# EasyEDA_esp8266-ed_fan_2020-07-05_01-05-.net
KiCad netlist of a schematic drawn in EasyEDA
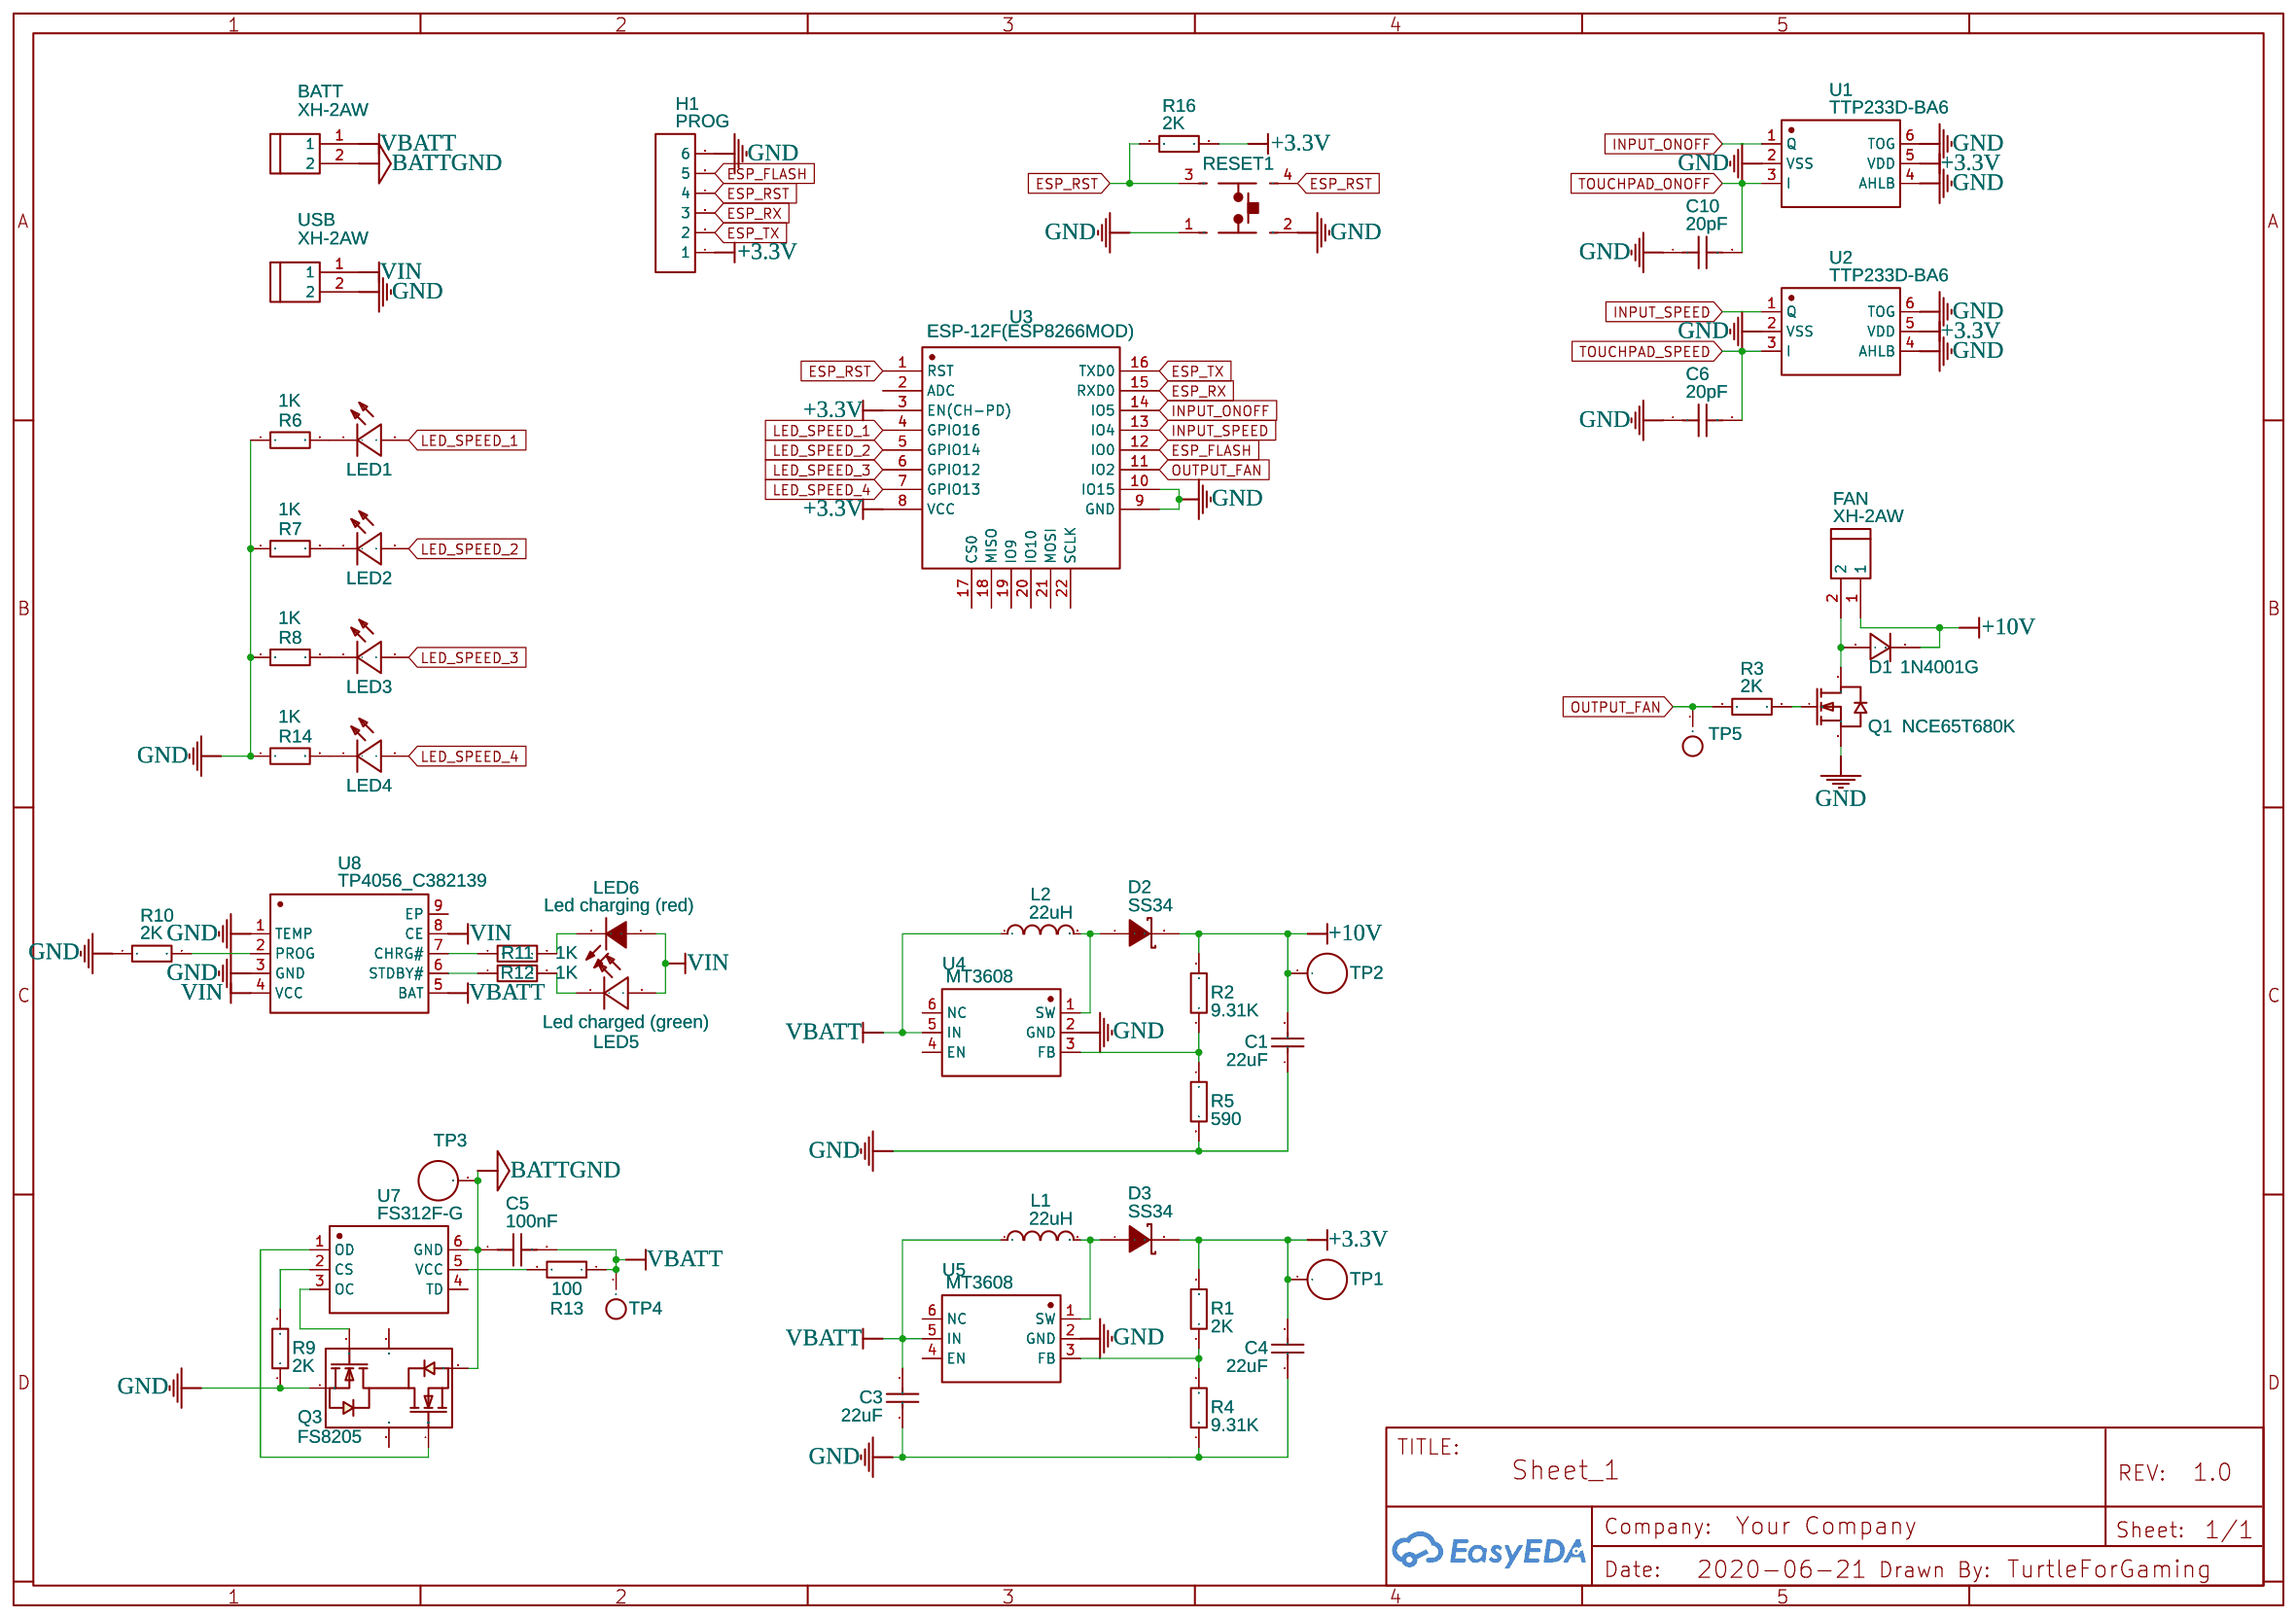
[diagram p0: schematic sheet]

(export (version "E")
  (design (tool "Eeschema 10.0.6"))
  (components
    (comp (ref "BATT")
      (value "XH-2AW")
      (fields (field (name "BOM_Supplier Part") "C33132"))
      (libsource (lib "") (part "XH-2AW"))
    )
    (comp (ref "C1")
      (value "22uF")
      (fields
        (field (name "BOM_Manufacturer Part") "1812X226K250NT")
        (field (name "BOM_Supplier Part") "C28504")
      )
      (libsource (lib "") (part "Unknown_645_-290"))
    )
    (comp (ref "C3")
      (value "22uF")
      (fields
        (field (name "BOM_Manufacturer Part") "1812X226K250NT")
        (field (name "BOM_Supplier Part") "C28504")
      )
      (libsource (lib "") (part "Unknown_450_-110"))
    )
    (comp (ref "C4")
      (value "22uF")
      (fields
        (field (name "BOM_Manufacturer Part") "1812X226K250NT")
        (field (name "BOM_Supplier Part") "C28504")
      )
      (libsource (lib "") (part "Unknown_645_-135"))
    )
    (comp (ref "C5")
      (value "100nF")
      (fields
        (field (name "BOM_Manufacturer Part") "GRM21BR72A104KAC4L")
        (field (name "BOM_Supplier Part") "C86044")
      )
      (libsource (lib "") (part "GRM21BR72A104KAC4L"))
    )
    (comp (ref "C6")
      (value "20pF")
      (fields
        (field (name "BOM_Manufacturer Part") "0603N200J500")
        (field (name "BOM_Supplier Part") "C123543")
      )
      (libsource (lib "") (part "0603N200J500"))
    )
    (comp (ref "C10")
      (value "20pF")
      (fields
        (field (name "BOM_Manufacturer Part") "0603N200J500")
        (field (name "BOM_Supplier Part") "C123543")
      )
      (libsource (lib "") (part "0603N200J500"))
    )
    (comp (ref "D1")
      (value "1N4001G")
      (fields (field (name "BOM_Supplier Part") "C433392"))
      (libsource (lib "") (part "1N4001G"))
    )
    (comp (ref "D2")
      (value "SS34")
      (fields (field (name "BOM_Supplier Part") "C8678"))
      (libsource (lib "") (part "Unknown_570_-340"))
    )
    (comp (ref "D3")
      (value "SS34")
      (fields (field (name "BOM_Supplier Part") "C8678"))
      (libsource (lib "") (part "Unknown_570_-185"))
    )
    (comp (ref "FAN")
      (value "XH-2AW")
      (fields (field (name "BOM_Supplier Part") "C33132"))
      (libsource (lib "") (part "XH-2AW_1"))
    )
    (comp (ref "H1")
      (value "PROG")
      (fields
        (field (name "BOM_Manufacturer Part") "Header-Male-2.54_1x6")
        (field (name "BOM_Supplier Part") "C37208")
      )
      (libsource (lib "") (part "Header-Male-2.54_1x6"))
    )
    (comp (ref "L1")
      (value "22uH")
      (fields
        (field (name "BOM_Manufacturer Part") "SMRH74-220MT")
        (field (name "BOM_Supplier Part") "C27442")
      )
      (libsource (lib "") (part "Unknown_520_-185"))
    )
    (comp (ref "L2")
      (value "22uH")
      (fields
        (field (name "BOM_Manufacturer Part") "SMRH74-220MT")
        (field (name "BOM_Supplier Part") "C27442")
      )
      (libsource (lib "") (part "Unknown_520_-340"))
    )
    (comp (ref "LED1")
      (value "Led charged (green)")
      (fields (field (name "BOM_Supplier Part") "C192319"))
      (libsource (lib "") (part "led Green"))
    )
    (comp (ref "LED2")
      (value "Led charged (green)")
      (fields (field (name "BOM_Supplier Part") "C192319"))
      (libsource (lib "") (part "led Green"))
    )
    (comp (ref "LED3")
      (value "Led charged (green)")
      (fields (field (name "BOM_Supplier Part") "C192319"))
      (libsource (lib "") (part "led Green"))
    )
    (comp (ref "LED4")
      (value "Led charged (green)")
      (fields (field (name "BOM_Supplier Part") "C192319"))
      (libsource (lib "") (part "led Green"))
    )
    (comp (ref "LED5")
      (value "Led charged (green)")
      (fields (field (name "BOM_Supplier Part") "C192319"))
      (libsource (lib "") (part "led Green"))
    )
    (comp (ref "LED6")
      (value "Led charging (red)")
      (fields (field (name "BOM_Supplier Part") "C192318"))
      (libsource (lib "") (part "KT-1206Red LED"))
    )
    (comp (ref "Q1")
      (value "NCE65T680K")
      (fields (field (name "BOM_Supplier Part") "C216787"))
      (libsource (lib "") (part "NCE65T680K"))
    )
    (comp (ref "Q3")
      (value "FS8205")
      (fields (field (name "BOM_Supplier Part") "C32254"))
      (libsource (lib "") (part "Unknown_190_-110"))
    )
    (comp (ref "R1")
      (value "2K")
      (fields
        (field (name "BOM_Manufacturer Part") "CR0805-FX-2001ELF")
        (field (name "BOM_Supplier Part") "C203834")
      )
      (libsource (lib "") (part "CR0805-FX-2001ELF"))
    )
    (comp (ref "R2")
      (value "9.31K")
      (fields
        (field (name "BOM_Manufacturer Part") "RMC08059.31K1%N")
        (field (name "BOM_Supplier Part") "C325873")
      )
      (libsource (lib "") (part "RMC08059.31K1%N"))
    )
    (comp (ref "R3")
      (value "2K")
      (fields
        (field (name "BOM_Manufacturer Part") "CR0805-FX-2001ELF")
        (field (name "BOM_Supplier Part") "C203834")
      )
      (libsource (lib "") (part "CR0805-FX-2001ELF_1"))
    )
    (comp (ref "R4")
      (value "9.31K")
      (fields
        (field (name "BOM_Manufacturer Part") "RMC08059.31K1%N")
        (field (name "BOM_Supplier Part") "C325873")
      )
      (libsource (lib "") (part "RMC08059.31K1%N"))
    )
    (comp (ref "R5")
      (value "590")
      (fields
        (field (name "BOM_Manufacturer Part") "CR0805F85900G")
        (field (name "BOM_Supplier Part") "C101801")
      )
      (libsource (lib "") (part "CR0805F85900G"))
    )
    (comp (ref "R6")
      (value "1K")
      (fields
        (field (name "BOM_Manufacturer Part") "CR0805J80102G")
        (field (name "BOM_Supplier Part") "C328385")
      )
      (libsource (lib "") (part "CR0805J80102G"))
    )
    (comp (ref "R7")
      (value "1K")
      (fields
        (field (name "BOM_Manufacturer Part") "CR0805J80102G")
        (field (name "BOM_Supplier Part") "C328385")
      )
      (libsource (lib "") (part "CR0805J80102G"))
    )
    (comp (ref "R8")
      (value "1K")
      (fields
        (field (name "BOM_Manufacturer Part") "CR0805J80102G")
        (field (name "BOM_Supplier Part") "C328385")
      )
      (libsource (lib "") (part "CR0805J80102G"))
    )
    (comp (ref "R9")
      (value "2K")
      (fields
        (field (name "BOM_Manufacturer Part") "CR0805-FX-2001ELF")
        (field (name "BOM_Supplier Part") "C203834")
      )
      (libsource (lib "") (part "CR0805-FX-2001ELF"))
    )
    (comp (ref "R10")
      (value "2K")
      (fields
        (field (name "BOM_Manufacturer Part") "CR0805-FX-2001ELF")
        (field (name "BOM_Supplier Part") "C203834")
      )
      (libsource (lib "") (part "CR0805-FX-2001ELF_2"))
    )
    (comp (ref "R11")
      (value "1K")
      (fields
        (field (name "BOM_Manufacturer Part") "CR0805J80102G")
        (field (name "BOM_Supplier Part") "C328385")
      )
      (libsource (lib "") (part "CR0805J80102G"))
    )
    (comp (ref "R12")
      (value "1K")
      (fields
        (field (name "BOM_Manufacturer Part") "CR0805J80102G")
        (field (name "BOM_Supplier Part") "C328385")
      )
      (libsource (lib "") (part "CR0805J80102G"))
    )
    (comp (ref "R13")
      (value "100")
      (fields
        (field (name "BOM_Manufacturer Part") "080500F1000T5E")
        (field (name "BOM_Supplier Part") "C146168")
      )
      (libsource (lib "") (part "080500F1000T5E"))
    )
    (comp (ref "R14")
      (value "1K")
      (fields
        (field (name "BOM_Manufacturer Part") "CR0805J80102G")
        (field (name "BOM_Supplier Part") "C328385")
      )
      (libsource (lib "") (part "CR0805J80102G"))
    )
    (comp (ref "R16")
      (value "2K")
      (fields
        (field (name "BOM_Manufacturer Part") "CR0805-FX-2001ELF")
        (field (name "BOM_Supplier Part") "C203834")
      )
      (libsource (lib "") (part "CR0805-FX-2001ELF_1"))
    )
    (comp (ref "RESET1")
      (value "RESET")
      (fields (field (name "BOM_Supplier Part") "C393938"))
      (libsource (lib "") (part "TACTILE SWITCH 6X6MM 11MM THT"))
    )
    (comp (ref "TP1")
      (value "TEST_PAD")
      (fields (field (name "BOM_Manufacturer Part") "TESTPAD"))
      (libsource (lib "") (part "TEST_PAD"))
    )
    (comp (ref "TP2")
      (value "TEST_PAD")
      (fields (field (name "BOM_Manufacturer Part") "TESTPAD"))
      (libsource (lib "") (part "TEST_PAD"))
    )
    (comp (ref "TP3")
      (value "TEST_PAD")
      (fields (field (name "BOM_Manufacturer Part") "TESTPAD"))
      (libsource (lib "") (part "TEST_PAD_2"))
    )
    (comp (ref "TP4")
      (value "TEST_PAD")
      (fields (field (name "BOM_Manufacturer Part") "TESTPAD"))
      (libsource (lib "") (part "TEST_PAD_1"))
    )
    (comp (ref "TP5")
      (value "TEST_PAD")
      (fields (field (name "BOM_Manufacturer Part") "TESTPAD"))
      (libsource (lib "") (part "TEST_PAD_1"))
    )
    (comp (ref "U1")
      (value "TTP233D-BA6")
      (fields (field (name "BOM_Supplier Part") "C82384"))
      (libsource (lib "") (part "TTP233D-BA6"))
    )
    (comp (ref "U2")
      (value "TTP233D-BA6")
      (fields (field (name "BOM_Supplier Part") "C82384"))
      (libsource (lib "") (part "TTP233D-BA6"))
    )
    (comp (ref "U3")
      (value "ESP-12F(ESP8266MOD)")
      (fields (field (name "BOM_Supplier Part") "C82891"))
      (libsource (lib "") (part "ESP-12F(ESP8266MOD)"))
    )
    (comp (ref "U4")
      (value "MT3608")
      (fields (field (name "BOM_Supplier Part") "C84817"))
      (libsource (lib "") (part "Unknown_510_-310"))
    )
    (comp (ref "U5")
      (value "MT3608")
      (fields (field (name "BOM_Supplier Part") "C84817"))
      (libsource (lib "") (part "Unknown_510_-155"))
    )
    (comp (ref "U7")
      (value "FS312F-G")
      (fields (field (name "BOM_Supplier Part") "C82736"))
      (libsource (lib "") (part "FS312F-G"))
    )
    (comp (ref "U8")
      (value "TP4056_C382139")
      (fields (field (name "BOM_Manufacturer Part") "TP4056") (field (name "BOM_Supplier Part") "C382139"))
      (libsource (lib "") (part "TP4056_C382139"))
    )
    (comp (ref "USB")
      (value "XH-2AW")
      (fields (field (name "BOM_Supplier Part") "C33132"))
      (libsource (lib "") (part "XH-2AW_2"))
    )
  )
  (nets
    (net (code "1") (name "+3.3V") (class "Default")
      (node (ref "C4") (pin "2") (pinfunction "2_2") (pintype "input"))
      (node (ref "D3") (pin "2") (pinfunction "K_2") (pintype "unspecified"))
      (node (ref "H1") (pin "1") (pinfunction "1_1") (pintype "input"))
      (node (ref "R1") (pin "2") (pinfunction "2_2") (pintype "unspecified"))
      (node (ref "R16") (pin "1") (pinfunction "1_1") (pintype "unspecified"))
      (node (ref "TP1") (pin "1") (pinfunction "1_1") (pintype "unspecified"))
      (node (ref "U1") (pin "5") (pinfunction "VDD_5") (pintype "unspecified"))
      (node (ref "U2") (pin "5") (pinfunction "VDD_5") (pintype "unspecified"))
      (node (ref "U3") (pin "3") (pinfunction "EN(CH-PD)_3") (pintype "unspecified"))
      (node (ref "U3") (pin "8") (pinfunction "VCC_8") (pintype "unspecified"))
    )
    (net (code "2") (name "+10V") (class "Default")
      (node (ref "C1") (pin "2") (pinfunction "2_2") (pintype "input"))
      (node (ref "D1") (pin "1") (pinfunction "C_1") (pintype "unspecified"))
      (node (ref "D2") (pin "2") (pinfunction "K_2") (pintype "unspecified"))
      (node (ref "FAN") (pin "1") (pinfunction "1_1") (pintype "unspecified"))
      (node (ref "R2") (pin "2") (pinfunction "2_2") (pintype "unspecified"))
      (node (ref "TP2") (pin "1") (pinfunction "1_1") (pintype "unspecified"))
    )
    (net (code "3") (name "BATTGND") (class "Default")
      (node (ref "BATT") (pin "2") (pinfunction "2_2") (pintype "unspecified"))
      (node (ref "C5") (pin "1") (pinfunction "1_1") (pintype "unspecified"))
      (node (ref "Q3") (pin "3") (pinfunction "S2_3") (pintype "unspecified"))
      (node (ref "TP3") (pin "1") (pinfunction "1_1") (pintype "unspecified"))
      (node (ref "U7") (pin "6") (pinfunction "GND_6") (pintype "unspecified"))
    )
    (net (code "4") (name "ESP_FLASH") (class "Default")
      (node (ref "H1") (pin "5") (pinfunction "5_5") (pintype "input"))
      (node (ref "U3") (pin "12") (pinfunction "IO0_12") (pintype "unspecified"))
    )
    (net (code "5") (name "ESP_RST") (class "Default")
      (node (ref "H1") (pin "4") (pinfunction "4_4") (pintype "input"))
      (node (ref "R16") (pin "2") (pinfunction "2_2") (pintype "unspecified"))
      (node (ref "RESET1") (pin "3") (pinfunction "3_3") (pintype "input"))
      (node (ref "RESET1") (pin "4") (pinfunction "4_4") (pintype "input"))
      (node (ref "U3") (pin "1") (pinfunction "RST_1") (pintype "unspecified"))
    )
    (net (code "6") (name "ESP_RX") (class "Default")
      (node (ref "H1") (pin "3") (pinfunction "3_3") (pintype "input"))
      (node (ref "U3") (pin "15") (pinfunction "RXD0_15") (pintype "unspecified"))
    )
    (net (code "7") (name "ESP_TX") (class "Default")
      (node (ref "H1") (pin "2") (pinfunction "2_2") (pintype "input"))
      (node (ref "U3") (pin "16") (pinfunction "TXD0_16") (pintype "unspecified"))
    )
    (net (code "8") (name "GND") (class "Default")
      (node (ref "C1") (pin "1") (pinfunction "1_1") (pintype "input"))
      (node (ref "C10") (pin "1") (pinfunction "1_1") (pintype "unspecified"))
      (node (ref "C3") (pin "1") (pinfunction "1_1") (pintype "input"))
      (node (ref "C4") (pin "1") (pinfunction "1_1") (pintype "input"))
      (node (ref "C6") (pin "1") (pinfunction "1_1") (pintype "unspecified"))
      (node (ref "H1") (pin "6") (pinfunction "6_6") (pintype "input"))
      (node (ref "Q1") (pin "3") (pinfunction "S_3") (pintype "unspecified"))
      (node (ref "Q3") (pin "1") (pinfunction "S1_1") (pintype "unspecified"))
      (node (ref "R10") (pin "1") (pinfunction "1_1") (pintype "unspecified"))
      (node (ref "R14") (pin "1") (pinfunction "1_1") (pintype "unspecified"))
      (node (ref "R4") (pin "1") (pinfunction "1_1") (pintype "unspecified"))
      (node (ref "R5") (pin "2") (pinfunction "2_2") (pintype "input"))
      (node (ref "R6") (pin "1") (pinfunction "1_1") (pintype "unspecified"))
      (node (ref "R7") (pin "1") (pinfunction "1_1") (pintype "unspecified"))
      (node (ref "R8") (pin "1") (pinfunction "1_1") (pintype "unspecified"))
      (node (ref "R9") (pin "1") (pinfunction "1_1") (pintype "unspecified"))
      (node (ref "RESET1") (pin "1") (pinfunction "1_1") (pintype "input"))
      (node (ref "RESET1") (pin "2") (pinfunction "2_2") (pintype "input"))
      (node (ref "U1") (pin "2") (pinfunction "VSS_2") (pintype "unspecified"))
      (node (ref "U1") (pin "4") (pinfunction "AHLB_4") (pintype "unspecified"))
      (node (ref "U1") (pin "6") (pinfunction "TOG_6") (pintype "unspecified"))
      (node (ref "U2") (pin "2") (pinfunction "VSS_2") (pintype "unspecified"))
      (node (ref "U2") (pin "4") (pinfunction "AHLB_4") (pintype "unspecified"))
      (node (ref "U2") (pin "6") (pinfunction "TOG_6") (pintype "unspecified"))
      (node (ref "U3") (pin "10") (pinfunction "IO15_10") (pintype "unspecified"))
      (node (ref "U3") (pin "9") (pinfunction "GND_9") (pintype "unspecified"))
      (node (ref "U4") (pin "2") (pinfunction "GND_2") (pintype "unspecified"))
      (node (ref "U5") (pin "2") (pinfunction "GND_2") (pintype "unspecified"))
      (node (ref "U8") (pin "1") (pinfunction "TEMP_1") (pintype "unspecified"))
      (node (ref "U8") (pin "3") (pinfunction "GND_3") (pintype "unspecified"))
      (node (ref "USB") (pin "2") (pinfunction "2_2") (pintype "unspecified"))
    )
    (net (code "9") (name "INPUT_ONOFF") (class "Default")
      (node (ref "U1") (pin "1") (pinfunction "Q_1") (pintype "unspecified"))
      (node (ref "U3") (pin "14") (pinfunction "IO5_14") (pintype "unspecified"))
    )
    (net (code "10") (name "INPUT_SPEED") (class "Default")
      (node (ref "U2") (pin "1") (pinfunction "Q_1") (pintype "unspecified"))
      (node (ref "U3") (pin "13") (pinfunction "IO4_13") (pintype "unspecified"))
    )
    (net (code "11") (name "LED_SPEED_1") (class "Default")
      (node (ref "LED1") (pin "2") (pinfunction "+_2") (pintype "unspecified"))
      (node (ref "U3") (pin "4") (pinfunction "GPIO16_4") (pintype "unspecified"))
    )
    (net (code "12") (name "LED_SPEED_2") (class "Default")
      (node (ref "LED2") (pin "2") (pinfunction "+_2") (pintype "unspecified"))
      (node (ref "U3") (pin "5") (pinfunction "GPIO14_5") (pintype "unspecified"))
    )
    (net (code "13") (name "LED_SPEED_3") (class "Default")
      (node (ref "LED3") (pin "2") (pinfunction "+_2") (pintype "unspecified"))
      (node (ref "U3") (pin "6") (pinfunction "GPIO12_6") (pintype "unspecified"))
    )
    (net (code "14") (name "LED_SPEED_4") (class "Default")
      (node (ref "LED4") (pin "2") (pinfunction "+_2") (pintype "unspecified"))
      (node (ref "U3") (pin "7") (pinfunction "GPIO13_7") (pintype "unspecified"))
    )
    (net (code "15") (name "Net-(D1-A)") (class "Default")
      (node (ref "D1") (pin "2") (pinfunction "A_2") (pintype "unspecified"))
      (node (ref "FAN") (pin "2") (pinfunction "2_2") (pintype "unspecified"))
      (node (ref "Q1") (pin "2") (pinfunction "D_2") (pintype "unspecified"))
    )
    (net (code "16") (name "Net-(D2-A)") (class "Default")
      (node (ref "D2") (pin "1") (pinfunction "A_1") (pintype "unspecified"))
      (node (ref "L2") (pin "2") (pinfunction "2_2") (pintype "unspecified"))
      (node (ref "U4") (pin "1") (pinfunction "SW_1") (pintype "unspecified"))
    )
    (net (code "17") (name "Net-(D3-A)") (class "Default")
      (node (ref "D3") (pin "1") (pinfunction "A_1") (pintype "unspecified"))
      (node (ref "L1") (pin "2") (pinfunction "2_2") (pintype "unspecified"))
      (node (ref "U5") (pin "1") (pinfunction "SW_1") (pintype "unspecified"))
    )
    (net (code "18") (name "Net-(LED1--)") (class "Default")
      (node (ref "LED1") (pin "1") (pinfunction "-_1") (pintype "unspecified"))
      (node (ref "R6") (pin "2") (pinfunction "2_2") (pintype "unspecified"))
    )
    (net (code "19") (name "Net-(LED2--)") (class "Default")
      (node (ref "LED2") (pin "1") (pinfunction "-_1") (pintype "unspecified"))
      (node (ref "R7") (pin "2") (pinfunction "2_2") (pintype "unspecified"))
    )
    (net (code "20") (name "Net-(LED3--)") (class "Default")
      (node (ref "LED3") (pin "1") (pinfunction "-_1") (pintype "unspecified"))
      (node (ref "R8") (pin "2") (pinfunction "2_2") (pintype "unspecified"))
    )
    (net (code "21") (name "Net-(LED4--)") (class "Default")
      (node (ref "LED4") (pin "1") (pinfunction "-_1") (pintype "unspecified"))
      (node (ref "R14") (pin "2") (pinfunction "2_2") (pintype "unspecified"))
    )
    (net (code "22") (name "Net-(LED5--)") (class "Default")
      (node (ref "LED5") (pin "1") (pinfunction "-_1") (pintype "unspecified"))
      (node (ref "R12") (pin "2") (pinfunction "2_2") (pintype "unspecified"))
    )
    (net (code "23") (name "Net-(LED6-K)") (class "Default")
      (node (ref "LED6") (pin "2") (pinfunction "K_2") (pintype "unspecified"))
      (node (ref "R11") (pin "2") (pinfunction "2_2") (pintype "unspecified"))
    )
    (net (code "24") (name "Net-(Q1-G)") (class "Default")
      (node (ref "Q1") (pin "1") (pinfunction "G_1") (pintype "unspecified"))
      (node (ref "R3") (pin "1") (pinfunction "1_1") (pintype "unspecified"))
    )
    (net (code "25") (name "Net-(Q3-G1)") (class "Default")
      (node (ref "Q3") (pin "6") (pinfunction "G1_6") (pintype "unspecified"))
      (node (ref "U7") (pin "3") (pinfunction "OC_3") (pintype "unspecified"))
    )
    (net (code "26") (name "Net-(Q3-G2)") (class "Default")
      (node (ref "Q3") (pin "4") (pinfunction "G2_4") (pintype "unspecified"))
      (node (ref "U7") (pin "1") (pinfunction "OD_1") (pintype "unspecified"))
    )
    (net (code "27") (name "Net-(U4-FB)") (class "Default")
      (node (ref "R2") (pin "1") (pinfunction "1_1") (pintype "unspecified"))
      (node (ref "R5") (pin "1") (pinfunction "1_1") (pintype "input"))
      (node (ref "U4") (pin "3") (pinfunction "FB_3") (pintype "unspecified"))
    )
    (net (code "28") (name "Net-(U5-FB)") (class "Default")
      (node (ref "R1") (pin "1") (pinfunction "1_1") (pintype "unspecified"))
      (node (ref "R4") (pin "2") (pinfunction "2_2") (pintype "unspecified"))
      (node (ref "U5") (pin "3") (pinfunction "FB_3") (pintype "unspecified"))
    )
    (net (code "29") (name "Net-(U7-CS)") (class "Default")
      (node (ref "R9") (pin "2") (pinfunction "2_2") (pintype "unspecified"))
      (node (ref "U7") (pin "2") (pinfunction "CS_2") (pintype "unspecified"))
    )
    (net (code "30") (name "Net-(U7-VCC)") (class "Default")
      (node (ref "R13") (pin "2") (pinfunction "2_2") (pintype "unspecified"))
      (node (ref "U7") (pin "5") (pinfunction "VCC_5") (pintype "unspecified"))
    )
    (net (code "31") (name "Net-(U8-CHRG#)") (class "Default")
      (node (ref "R11") (pin "1") (pinfunction "1_1") (pintype "unspecified"))
      (node (ref "U8") (pin "7") (pinfunction "CHRG#_7") (pintype "unspecified"))
    )
    (net (code "32") (name "Net-(U8-PROG)") (class "Default")
      (node (ref "R10") (pin "2") (pinfunction "2_2") (pintype "unspecified"))
      (node (ref "U8") (pin "2") (pinfunction "PROG_2") (pintype "unspecified"))
    )
    (net (code "33") (name "Net-(U8-STDBY#)") (class "Default")
      (node (ref "R12") (pin "1") (pinfunction "1_1") (pintype "unspecified"))
      (node (ref "U8") (pin "6") (pinfunction "STDBY#_6") (pintype "unspecified"))
    )
    (net (code "34") (name "OUTPUT_FAN") (class "Default")
      (node (ref "R3") (pin "2") (pinfunction "2_2") (pintype "unspecified"))
      (node (ref "TP5") (pin "1") (pinfunction "1_1") (pintype "unspecified"))
      (node (ref "U3") (pin "11") (pinfunction "IO2_11") (pintype "unspecified"))
    )
    (net (code "35") (name "TOUCHPAD_ONOFF") (class "Default")
      (node (ref "C10") (pin "2") (pinfunction "2_2") (pintype "unspecified"))
      (node (ref "U1") (pin "3") (pinfunction "I_3") (pintype "unspecified"))
    )
    (net (code "36") (name "TOUCHPAD_SPEED") (class "Default")
      (node (ref "C6") (pin "2") (pinfunction "2_2") (pintype "unspecified"))
      (node (ref "U2") (pin "3") (pinfunction "I_3") (pintype "unspecified"))
    )
    (net (code "37") (name "VBATT") (class "Default")
      (node (ref "BATT") (pin "1") (pinfunction "1_1") (pintype "unspecified"))
      (node (ref "C3") (pin "2") (pinfunction "2_2") (pintype "input"))
      (node (ref "C5") (pin "2") (pinfunction "2_2") (pintype "unspecified"))
      (node (ref "L1") (pin "1") (pinfunction "1_1") (pintype "unspecified"))
      (node (ref "L2") (pin "1") (pinfunction "1_1") (pintype "unspecified"))
      (node (ref "R13") (pin "1") (pinfunction "1_1") (pintype "unspecified"))
      (node (ref "TP4") (pin "1") (pinfunction "1_1") (pintype "unspecified"))
      (node (ref "U4") (pin "5") (pinfunction "IN_5") (pintype "unspecified"))
      (node (ref "U5") (pin "5") (pinfunction "IN_5") (pintype "unspecified"))
      (node (ref "U8") (pin "5") (pinfunction "BAT_5") (pintype "unspecified"))
    )
    (net (code "38") (name "VIN") (class "Default")
      (node (ref "LED5") (pin "2") (pinfunction "+_2") (pintype "unspecified"))
      (node (ref "LED6") (pin "1") (pinfunction "A_1") (pintype "unspecified"))
      (node (ref "U8") (pin "4") (pinfunction "VCC_4") (pintype "unspecified"))
      (node (ref "U8") (pin "8") (pinfunction "CE_8") (pintype "unspecified"))
      (node (ref "USB") (pin "1") (pinfunction "1_1") (pintype "unspecified"))
    )
    (net (code "39") (name "unconnected-(Q3-D12-Pad2)") (class "Default")
      (node (ref "Q3") (pin "2") (pinfunction "D12_2") (pintype "unspecified"))
    )
    (net (code "40") (name "unconnected-(Q3-D12-Pad5)") (class "Default")
      (node (ref "Q3") (pin "5") (pinfunction "D12_5") (pintype "unspecified"))
    )
    (net (code "41") (name "unconnected-(U3-ADC-Pad2)") (class "Default")
      (node (ref "U3") (pin "2") (pinfunction "ADC_2") (pintype "unspecified"))
    )
    (net (code "42") (name "unconnected-(U3-CS0-Pad17)") (class "Default")
      (node (ref "U3") (pin "17") (pinfunction "CS0_17") (pintype "unspecified"))
    )
    (net (code "43") (name "unconnected-(U3-IO9-Pad19)") (class "Default")
      (node (ref "U3") (pin "19") (pinfunction "IO9_19") (pintype "unspecified"))
    )
    (net (code "44") (name "unconnected-(U3-IO10-Pad20)") (class "Default")
      (node (ref "U3") (pin "20") (pinfunction "IO10_20") (pintype "unspecified"))
    )
    (net (code "45") (name "unconnected-(U3-MISO-Pad18)") (class "Default")
      (node (ref "U3") (pin "18") (pinfunction "MISO_18") (pintype "unspecified"))
    )
    (net (code "46") (name "unconnected-(U3-MOSI-Pad21)") (class "Default")
      (node (ref "U3") (pin "21") (pinfunction "MOSI_21") (pintype "unspecified"))
    )
    (net (code "47") (name "unconnected-(U3-SCLK-Pad22)") (class "Default")
      (node (ref "U3") (pin "22") (pinfunction "SCLK_22") (pintype "unspecified"))
    )
    (net (code "48") (name "unconnected-(U4-EN-Pad4)") (class "Default")
      (node (ref "U4") (pin "4") (pinfunction "EN_4") (pintype "unspecified"))
    )
    (net (code "49") (name "unconnected-(U4-NC-Pad6)") (class "Default")
      (node (ref "U4") (pin "6") (pinfunction "NC_6") (pintype "unspecified"))
    )
    (net (code "50") (name "unconnected-(U5-EN-Pad4)") (class "Default")
      (node (ref "U5") (pin "4") (pinfunction "EN_4") (pintype "unspecified"))
    )
    (net (code "51") (name "unconnected-(U5-NC-Pad6)") (class "Default")
      (node (ref "U5") (pin "6") (pinfunction "NC_6") (pintype "unspecified"))
    )
    (net (code "52") (name "unconnected-(U7-TD-Pad4)") (class "Default")
      (node (ref "U7") (pin "4") (pinfunction "TD_4") (pintype "unspecified"))
    )
    (net (code "53") (name "unconnected-(U8-EP-Pad9)") (class "Default")
      (node (ref "U8") (pin "9") (pinfunction "EP_9") (pintype "unspecified"))
    )
  )
)
